# xyshield_final.net
KiCad netlist of a schematic drawn in EAGLE
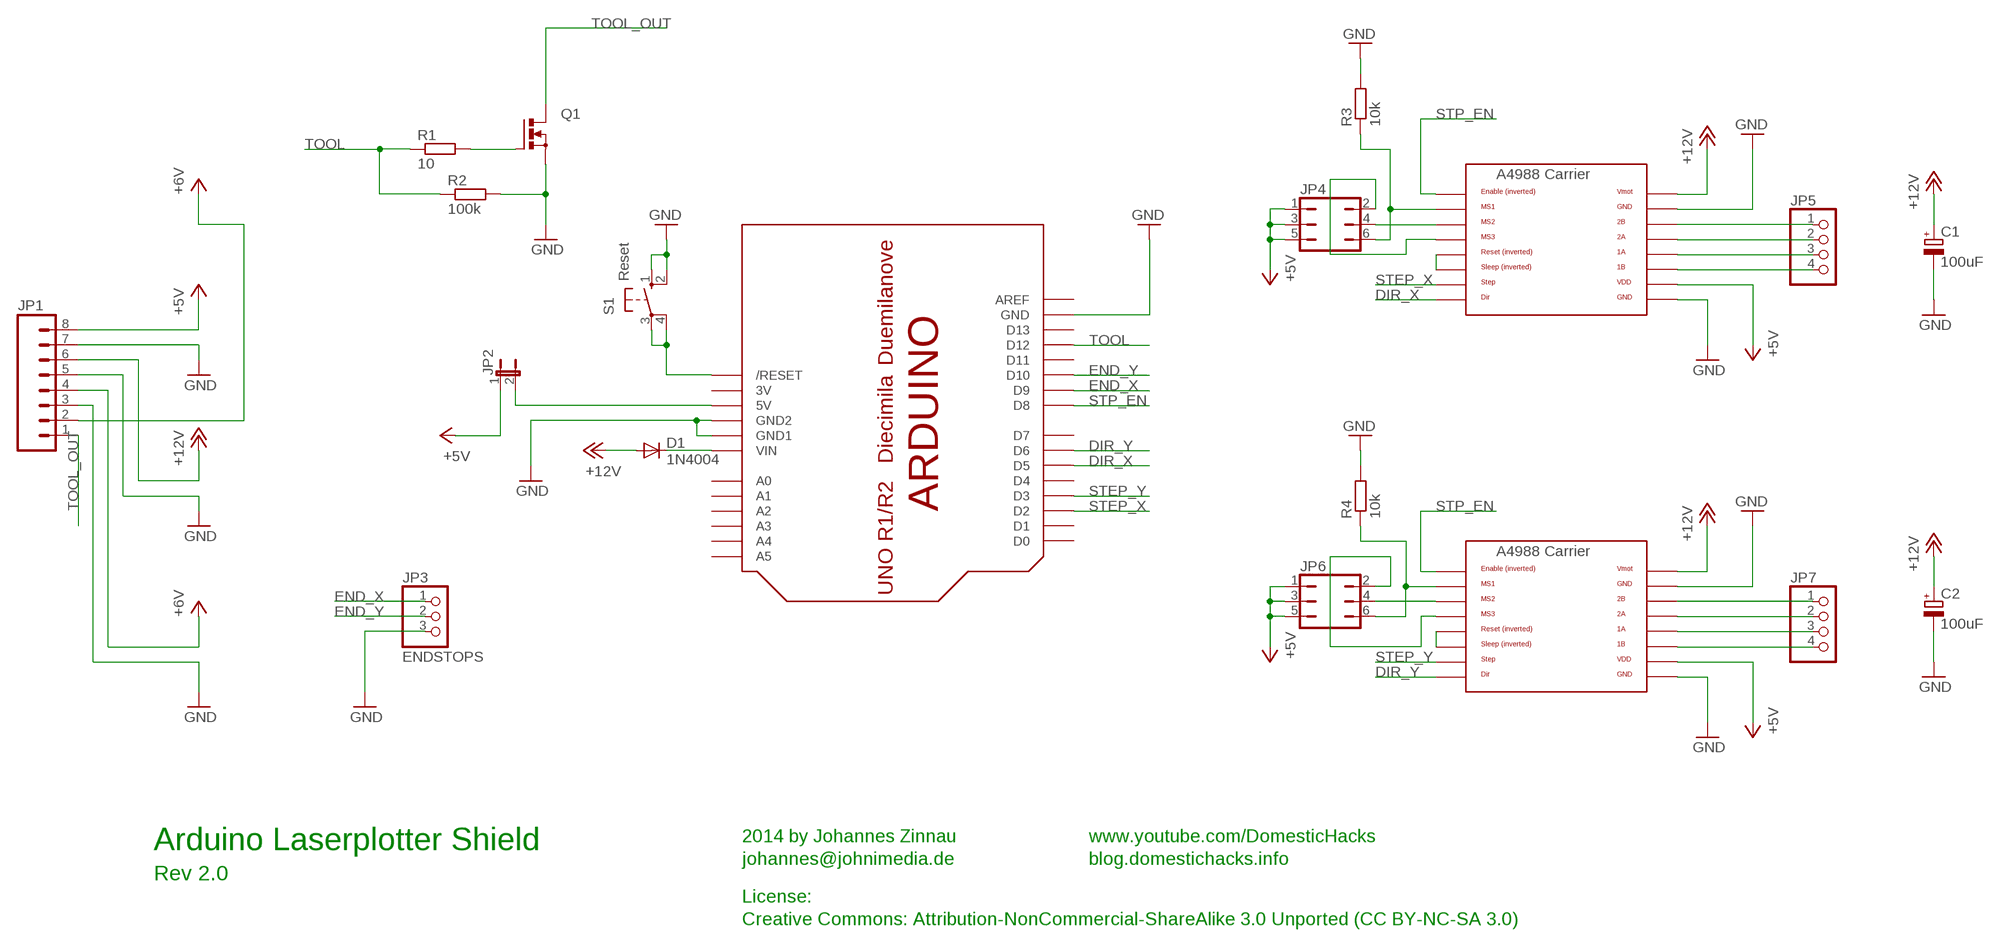
[diagram p0: schematic, sheet 1]

(export (version "E")
  (design (tool "Eeschema 10.0.6"))
  (components
    (comp (ref "C1")
      (value "100uF")
      (footprint "eagle-import:E2,5-6")
      (libsource (lib "eagle-import") (part "CPOL-EUE2.5-6"))
    )
    (comp (ref "C2")
      (value "100uF")
      (footprint "eagle-import:E2,5-6")
      (libsource (lib "eagle-import") (part "CPOL-EUE2.5-6"))
    )
    (comp (ref "D1")
      (value "1N4004")
      (footprint "eagle-import:DO41-10")
      (libsource (lib "eagle-import") (part "1N4004"))
    )
    (comp (ref "JP1")
      (value "M083.5MM-8")
      (footprint "eagle-import:SCREWTERMINAL-3.5MM-8")
      (libsource (lib "eagle-import") (part "M083.5MM-8"))
    )
    (comp (ref "JP2")
      (value "JUMPER-2PTH")
      (footprint "eagle-import:1X02")
      (libsource (lib "eagle-import") (part "JUMPER-2PTH"))
    )
    (comp (ref "JP3")
      (value "ENDSTOPS")
      (footprint "eagle-import:1X03")
      (libsource (lib "eagle-import") (part "PINHD-1X3"))
    )
    (comp (ref "JP4")
      (value "JP3Q")
      (footprint "eagle-import:JP3Q")
      (libsource (lib "eagle-import") (part "JP3Q"))
    )
    (comp (ref "JP5")
      (value "PINHD-1X4")
      (footprint "eagle-import:1X04")
      (libsource (lib "eagle-import") (part "PINHD-1X4"))
    )
    (comp (ref "JP6")
      (value "JP3Q")
      (footprint "eagle-import:JP3Q")
      (libsource (lib "eagle-import") (part "JP3Q"))
    )
    (comp (ref "JP7")
      (value "PINHD-1X4")
      (footprint "eagle-import:1X04")
      (libsource (lib "eagle-import") (part "PINHD-1X4"))
    )
    (comp (ref "Q1")
      (value "PMOSFET_NTO220BV")
      (footprint "eagle-import:TO220BV")
      (libsource (lib "eagle-import") (part "PMOSFET_NTO220BV"))
    )
    (comp (ref "R1")
      (value "10")
      (footprint "eagle-import:0207_10")
      (libsource (lib "eagle-import") (part "R-EU_0207/10"))
    )
    (comp (ref "R2")
      (value "100k")
      (footprint "eagle-import:0207_10")
      (libsource (lib "eagle-import") (part "R-EU_0207/10"))
    )
    (comp (ref "R3")
      (value "10k")
      (footprint "eagle-import:0207_2V")
      (libsource (lib "eagle-import") (part "R-EU_0207/2V"))
    )
    (comp (ref "R4")
      (value "10k")
      (footprint "eagle-import:0207_2V")
      (libsource (lib "eagle-import") (part "R-EU_0207/2V"))
    )
    (comp (ref "S1")
      (value "Reset")
      (footprint "eagle-import:B3F-10XX")
      (fields (field (name "MPN") "B3F-1000"))
      (libsource (lib "eagle-import") (part "10-XX"))
    )
    (comp (ref "U$1")
      (value "POLOLU_A4983CARRIER")
      (footprint "eagle-import:A4988BREAKOUT")
      (libsource (lib "eagle-import") (part "POLOLU_A4983CARRIER"))
    )
    (comp (ref "U$2")
      (value "POLOLU_A4983CARRIER")
      (footprint "eagle-import:A4988BREAKOUT")
      (libsource (lib "eagle-import") (part "POLOLU_A4983CARRIER"))
    )
    (comp (ref "U$3")
      (value "ARDUINOUNO")
      (footprint "eagle-import:ARDUINO")
      (libsource (lib "eagle-import") (part "ARDUINOUNO"))
    )
  )
  (nets
    (net (code "1") (name "+5V") (class "Default")
      (node (ref "JP1") (pin "8") (pinfunction "8_8") (pintype "passive"))
      (node (ref "JP2") (pin "1") (pinfunction "1_1") (pintype "passive"))
      (node (ref "JP4") (pin "1") (pinfunction "1_1") (pintype "passive"))
      (node (ref "JP4") (pin "3") (pinfunction "3_3") (pintype "passive"))
      (node (ref "JP4") (pin "5") (pinfunction "5_5") (pintype "passive"))
      (node (ref "JP6") (pin "1") (pinfunction "1_1") (pintype "passive"))
      (node (ref "JP6") (pin "3") (pinfunction "3_3") (pintype "passive"))
      (node (ref "JP6") (pin "5") (pinfunction "5_5") (pintype "passive"))
      (node (ref "U$1") (pin "VDD") (pinfunction "VDD_VDD") (pintype "power_in"))
      (node (ref "U$2") (pin "VDD") (pinfunction "VDD_VDD") (pintype "power_in"))
    )
    (net (code "2") (name "+6V") (class "Default")
      (node (ref "JP1") (pin "2") (pinfunction "2_2") (pintype "passive"))
      (node (ref "JP1") (pin "4") (pinfunction "4_4") (pintype "passive"))
    )
    (net (code "3") (name "+12V") (class "Default")
      (node (ref "C1") (pin "+") (pinfunction "+_+") (pintype "passive"))
      (node (ref "C2") (pin "+") (pinfunction "+_+") (pintype "passive"))
      (node (ref "D1") (pin "A") (pinfunction "A_A") (pintype "passive"))
      (node (ref "JP1") (pin "6") (pinfunction "6_6") (pintype "passive"))
      (node (ref "U$1") (pin "VMOT") (pinfunction "VMOT_VMOT") (pintype "power_in"))
      (node (ref "U$2") (pin "VMOT") (pinfunction "VMOT_VMOT") (pintype "power_in"))
    )
    (net (code "4") (name "/3V") (class "Default")
      (node (ref "U$3") (pin "3V") (pinfunction "3V_3V") (pintype "power_in"))
    )
    (net (code "5") (name "/DIR_X") (class "Default")
      (node (ref "U$1") (pin "DIR") (pinfunction "DIR_DIR") (pintype "input"))
      (node (ref "U$3") (pin "D5") (pinfunction "D5_D5") (pintype "bidirectional"))
    )
    (net (code "6") (name "/DIR_Y") (class "Default")
      (node (ref "U$2") (pin "DIR") (pinfunction "DIR_DIR") (pintype "input"))
      (node (ref "U$3") (pin "D6") (pinfunction "D6_D6") (pintype "bidirectional"))
    )
    (net (code "7") (name "/END_X") (class "Default")
      (node (ref "JP3") (pin "1") (pinfunction "1_1") (pintype "passive"))
      (node (ref "U$3") (pin "D9") (pinfunction "D9_D9") (pintype "bidirectional"))
    )
    (net (code "8") (name "/END_Y") (class "Default")
      (node (ref "JP3") (pin "2") (pinfunction "2_2") (pintype "passive"))
      (node (ref "U$3") (pin "D10") (pinfunction "D10_D10") (pintype "bidirectional"))
    )
    (net (code "9") (name "/STEP_X") (class "Default")
      (node (ref "U$1") (pin "STEP") (pinfunction "STEP_STEP") (pintype "input"))
      (node (ref "U$3") (pin "D2") (pinfunction "D2_D2") (pintype "bidirectional"))
    )
    (net (code "10") (name "/STEP_Y") (class "Default")
      (node (ref "U$2") (pin "STEP") (pinfunction "STEP_STEP") (pintype "input"))
      (node (ref "U$3") (pin "D3") (pinfunction "D3_D3") (pintype "bidirectional"))
    )
    (net (code "11") (name "/STP_EN") (class "Default")
      (node (ref "U$1") (pin "EN") (pinfunction "EN_EN") (pintype "input"))
      (node (ref "U$2") (pin "EN") (pinfunction "EN_EN") (pintype "input"))
      (node (ref "U$3") (pin "D8") (pinfunction "D8_D8") (pintype "bidirectional"))
    )
    (net (code "12") (name "/TOOL") (class "Default")
      (node (ref "R1") (pin "1") (pinfunction "1_1") (pintype "passive"))
      (node (ref "R2") (pin "1") (pinfunction "1_1") (pintype "passive"))
      (node (ref "U$3") (pin "D12") (pinfunction "D12_D12") (pintype "bidirectional"))
    )
    (net (code "13") (name "/TOOL_OUT") (class "Default")
      (node (ref "JP1") (pin "1") (pinfunction "1_1") (pintype "passive"))
      (node (ref "Q1") (pin "D") (pinfunction "D_D") (pintype "passive"))
    )
    (net (code "14") (name "GND") (class "Default")
      (node (ref "C1") (pin "-") (pinfunction "-_-") (pintype "passive"))
      (node (ref "C2") (pin "-") (pinfunction "-_-") (pintype "passive"))
      (node (ref "JP1") (pin "3") (pinfunction "3_3") (pintype "passive"))
      (node (ref "JP1") (pin "5") (pinfunction "5_5") (pintype "passive"))
      (node (ref "JP1") (pin "7") (pinfunction "7_7") (pintype "passive"))
      (node (ref "JP3") (pin "3") (pinfunction "3_3") (pintype "passive"))
      (node (ref "Q1") (pin "S") (pinfunction "S_S") (pintype "passive"))
      (node (ref "R2") (pin "2") (pinfunction "2_2") (pintype "passive"))
      (node (ref "R3") (pin "2") (pinfunction "2_2") (pintype "passive"))
      (node (ref "R4") (pin "2") (pinfunction "2_2") (pintype "passive"))
      (node (ref "S1") (pin "1") (pinfunction "S_1") (pintype "passive"))
      (node (ref "S1") (pin "2") (pinfunction "S1_2") (pintype "passive"))
      (node (ref "U$1") (pin "GND") (pinfunction "GND_GND") (pintype "power_in"))
      (node (ref "U$1") (pin "GND@0") (pinfunction "GND_GND@0") (pintype "power_in"))
      (node (ref "U$2") (pin "GND") (pinfunction "GND_GND") (pintype "power_in"))
      (node (ref "U$2") (pin "GND@0") (pinfunction "GND_GND@0") (pintype "power_in"))
      (node (ref "U$3") (pin "GND") (pinfunction "GND_GND") (pintype "power_in"))
      (node (ref "U$3") (pin "GND1") (pinfunction "GND1_GND1") (pintype "power_in"))
      (node (ref "U$3") (pin "GND2") (pinfunction "GND2_GND2") (pintype "power_in"))
    )
    (net (code "15") (name "Net-(D1-PadC)") (class "Default")
      (node (ref "D1") (pin "C") (pinfunction "C_C") (pintype "passive"))
      (node (ref "U$3") (pin "VIN") (pinfunction "VIN_VIN") (pintype "power_in"))
    )
    (net (code "16") (name "Net-(JP2-Pad2)") (class "Default")
      (node (ref "JP2") (pin "2") (pinfunction "2_2") (pintype "passive"))
      (node (ref "U$3") (pin "5V") (pinfunction "5V_5V") (pintype "power_in"))
    )
    (net (code "17") (name "Net-(JP4-Pad2)") (class "Default")
      (node (ref "JP4") (pin "2") (pinfunction "2_2") (pintype "passive"))
      (node (ref "U$1") (pin "MS3") (pinfunction "MS3_MS3") (pintype "input"))
    )
    (net (code "18") (name "Net-(JP4-Pad4)") (class "Default")
      (node (ref "JP4") (pin "4") (pinfunction "4_4") (pintype "passive"))
      (node (ref "U$1") (pin "MS2") (pinfunction "MS2_MS2") (pintype "input"))
    )
    (net (code "19") (name "Net-(JP4-Pad6)") (class "Default")
      (node (ref "JP4") (pin "6") (pinfunction "6_6") (pintype "passive"))
      (node (ref "R3") (pin "1") (pinfunction "1_1") (pintype "passive"))
      (node (ref "U$1") (pin "MS1") (pinfunction "MS1_MS1") (pintype "input"))
    )
    (net (code "20") (name "Net-(JP5-Pad1)") (class "Default")
      (node (ref "JP5") (pin "1") (pinfunction "1_1") (pintype "passive"))
      (node (ref "U$1") (pin "2B") (pinfunction "2B_2B") (pintype "output"))
    )
    (net (code "21") (name "Net-(JP5-Pad2)") (class "Default")
      (node (ref "JP5") (pin "2") (pinfunction "2_2") (pintype "passive"))
      (node (ref "U$1") (pin "2A") (pinfunction "2A_2A") (pintype "output"))
    )
    (net (code "22") (name "Net-(JP5-Pad3)") (class "Default")
      (node (ref "JP5") (pin "3") (pinfunction "3_3") (pintype "passive"))
      (node (ref "U$1") (pin "1A") (pinfunction "1A_1A") (pintype "output"))
    )
    (net (code "23") (name "Net-(JP5-Pad4)") (class "Default")
      (node (ref "JP5") (pin "4") (pinfunction "4_4") (pintype "passive"))
      (node (ref "U$1") (pin "1B") (pinfunction "1B_1B") (pintype "output"))
    )
    (net (code "24") (name "Net-(JP6-Pad2)") (class "Default")
      (node (ref "JP6") (pin "2") (pinfunction "2_2") (pintype "passive"))
      (node (ref "U$2") (pin "MS3") (pinfunction "MS3_MS3") (pintype "input"))
    )
    (net (code "25") (name "Net-(JP6-Pad4)") (class "Default")
      (node (ref "JP6") (pin "4") (pinfunction "4_4") (pintype "passive"))
      (node (ref "U$2") (pin "MS2") (pinfunction "MS2_MS2") (pintype "input"))
    )
    (net (code "26") (name "Net-(JP6-Pad6)") (class "Default")
      (node (ref "JP6") (pin "6") (pinfunction "6_6") (pintype "passive"))
      (node (ref "R4") (pin "1") (pinfunction "1_1") (pintype "passive"))
      (node (ref "U$2") (pin "MS1") (pinfunction "MS1_MS1") (pintype "input"))
    )
    (net (code "27") (name "Net-(JP7-Pad1)") (class "Default")
      (node (ref "JP7") (pin "1") (pinfunction "1_1") (pintype "passive"))
      (node (ref "U$2") (pin "2B") (pinfunction "2B_2B") (pintype "output"))
    )
    (net (code "28") (name "Net-(JP7-Pad2)") (class "Default")
      (node (ref "JP7") (pin "2") (pinfunction "2_2") (pintype "passive"))
      (node (ref "U$2") (pin "2A") (pinfunction "2A_2A") (pintype "output"))
    )
    (net (code "29") (name "Net-(JP7-Pad3)") (class "Default")
      (node (ref "JP7") (pin "3") (pinfunction "3_3") (pintype "passive"))
      (node (ref "U$2") (pin "1A") (pinfunction "1A_1A") (pintype "output"))
    )
    (net (code "30") (name "Net-(JP7-Pad4)") (class "Default")
      (node (ref "JP7") (pin "4") (pinfunction "4_4") (pintype "passive"))
      (node (ref "U$2") (pin "1B") (pinfunction "1B_1B") (pintype "output"))
    )
    (net (code "31") (name "Net-(Q1-PadG)") (class "Default")
      (node (ref "Q1") (pin "G") (pinfunction "G_G") (pintype "passive"))
      (node (ref "R1") (pin "2") (pinfunction "2_2") (pintype "passive"))
    )
    (net (code "32") (name "Net-(S1-P)") (class "Default")
      (node (ref "S1") (pin "3") (pinfunction "P_3") (pintype "passive"))
      (node (ref "S1") (pin "4") (pinfunction "P1_4") (pintype "passive"))
      (node (ref "U$3") (pin "RESET") (pinfunction "/RESET_RESET") (pintype "bidirectional"))
    )
    (net (code "33") (name "Net-(U$1-SLEEP)") (class "Default")
      (node (ref "U$1") (pin "RST") (pinfunction "RST_RST") (pintype "input"))
      (node (ref "U$1") (pin "SLP") (pinfunction "SLEEP_SLP") (pintype "input"))
    )
    (net (code "34") (name "Net-(U$2-SLEEP)") (class "Default")
      (node (ref "U$2") (pin "RST") (pinfunction "RST_RST") (pintype "input"))
      (node (ref "U$2") (pin "SLP") (pinfunction "SLEEP_SLP") (pintype "input"))
    )
    (net (code "35") (name "unconnected-(U$3-PadA0)") (class "Default")
      (node (ref "U$3") (pin "A0") (pinfunction "A0_A0") (pintype "bidirectional"))
    )
    (net (code "36") (name "unconnected-(U$3-PadA1)") (class "Default")
      (node (ref "U$3") (pin "A1") (pinfunction "A1_A1") (pintype "bidirectional"))
    )
    (net (code "37") (name "unconnected-(U$3-PadA2)") (class "Default")
      (node (ref "U$3") (pin "A2") (pinfunction "A2_A2") (pintype "bidirectional"))
    )
    (net (code "38") (name "unconnected-(U$3-PadA3)") (class "Default")
      (node (ref "U$3") (pin "A3") (pinfunction "A3_A3") (pintype "bidirectional"))
    )
    (net (code "39") (name "unconnected-(U$3-PadA4)") (class "Default")
      (node (ref "U$3") (pin "A4") (pinfunction "A4_A4") (pintype "bidirectional"))
    )
    (net (code "40") (name "unconnected-(U$3-PadA5)") (class "Default")
      (node (ref "U$3") (pin "A5") (pinfunction "A5_A5") (pintype "bidirectional"))
    )
    (net (code "41") (name "unconnected-(U$3-PadAREF)") (class "Default")
      (node (ref "U$3") (pin "AREF") (pinfunction "AREF_AREF") (pintype "bidirectional"))
    )
    (net (code "42") (name "unconnected-(U$3-PadD0)") (class "Default")
      (node (ref "U$3") (pin "D0") (pinfunction "D0_D0") (pintype "bidirectional"))
    )
    (net (code "43") (name "unconnected-(U$3-PadD1)") (class "Default")
      (node (ref "U$3") (pin "D1") (pinfunction "D1_D1") (pintype "bidirectional"))
    )
    (net (code "44") (name "unconnected-(U$3-PadD4)") (class "Default")
      (node (ref "U$3") (pin "D4") (pinfunction "D4_D4") (pintype "bidirectional"))
    )
    (net (code "45") (name "unconnected-(U$3-PadD7)") (class "Default")
      (node (ref "U$3") (pin "D7") (pinfunction "D7_D7") (pintype "bidirectional"))
    )
    (net (code "46") (name "unconnected-(U$3-PadD11)") (class "Default")
      (node (ref "U$3") (pin "D11") (pinfunction "D11_D11") (pintype "bidirectional"))
    )
    (net (code "47") (name "unconnected-(U$3-PadD13)") (class "Default")
      (node (ref "U$3") (pin "D13") (pinfunction "D13_D13") (pintype "bidirectional"))
    )
  )
)
